# 2.net
KiCad netlist of a schematic drawn in Altium Designer
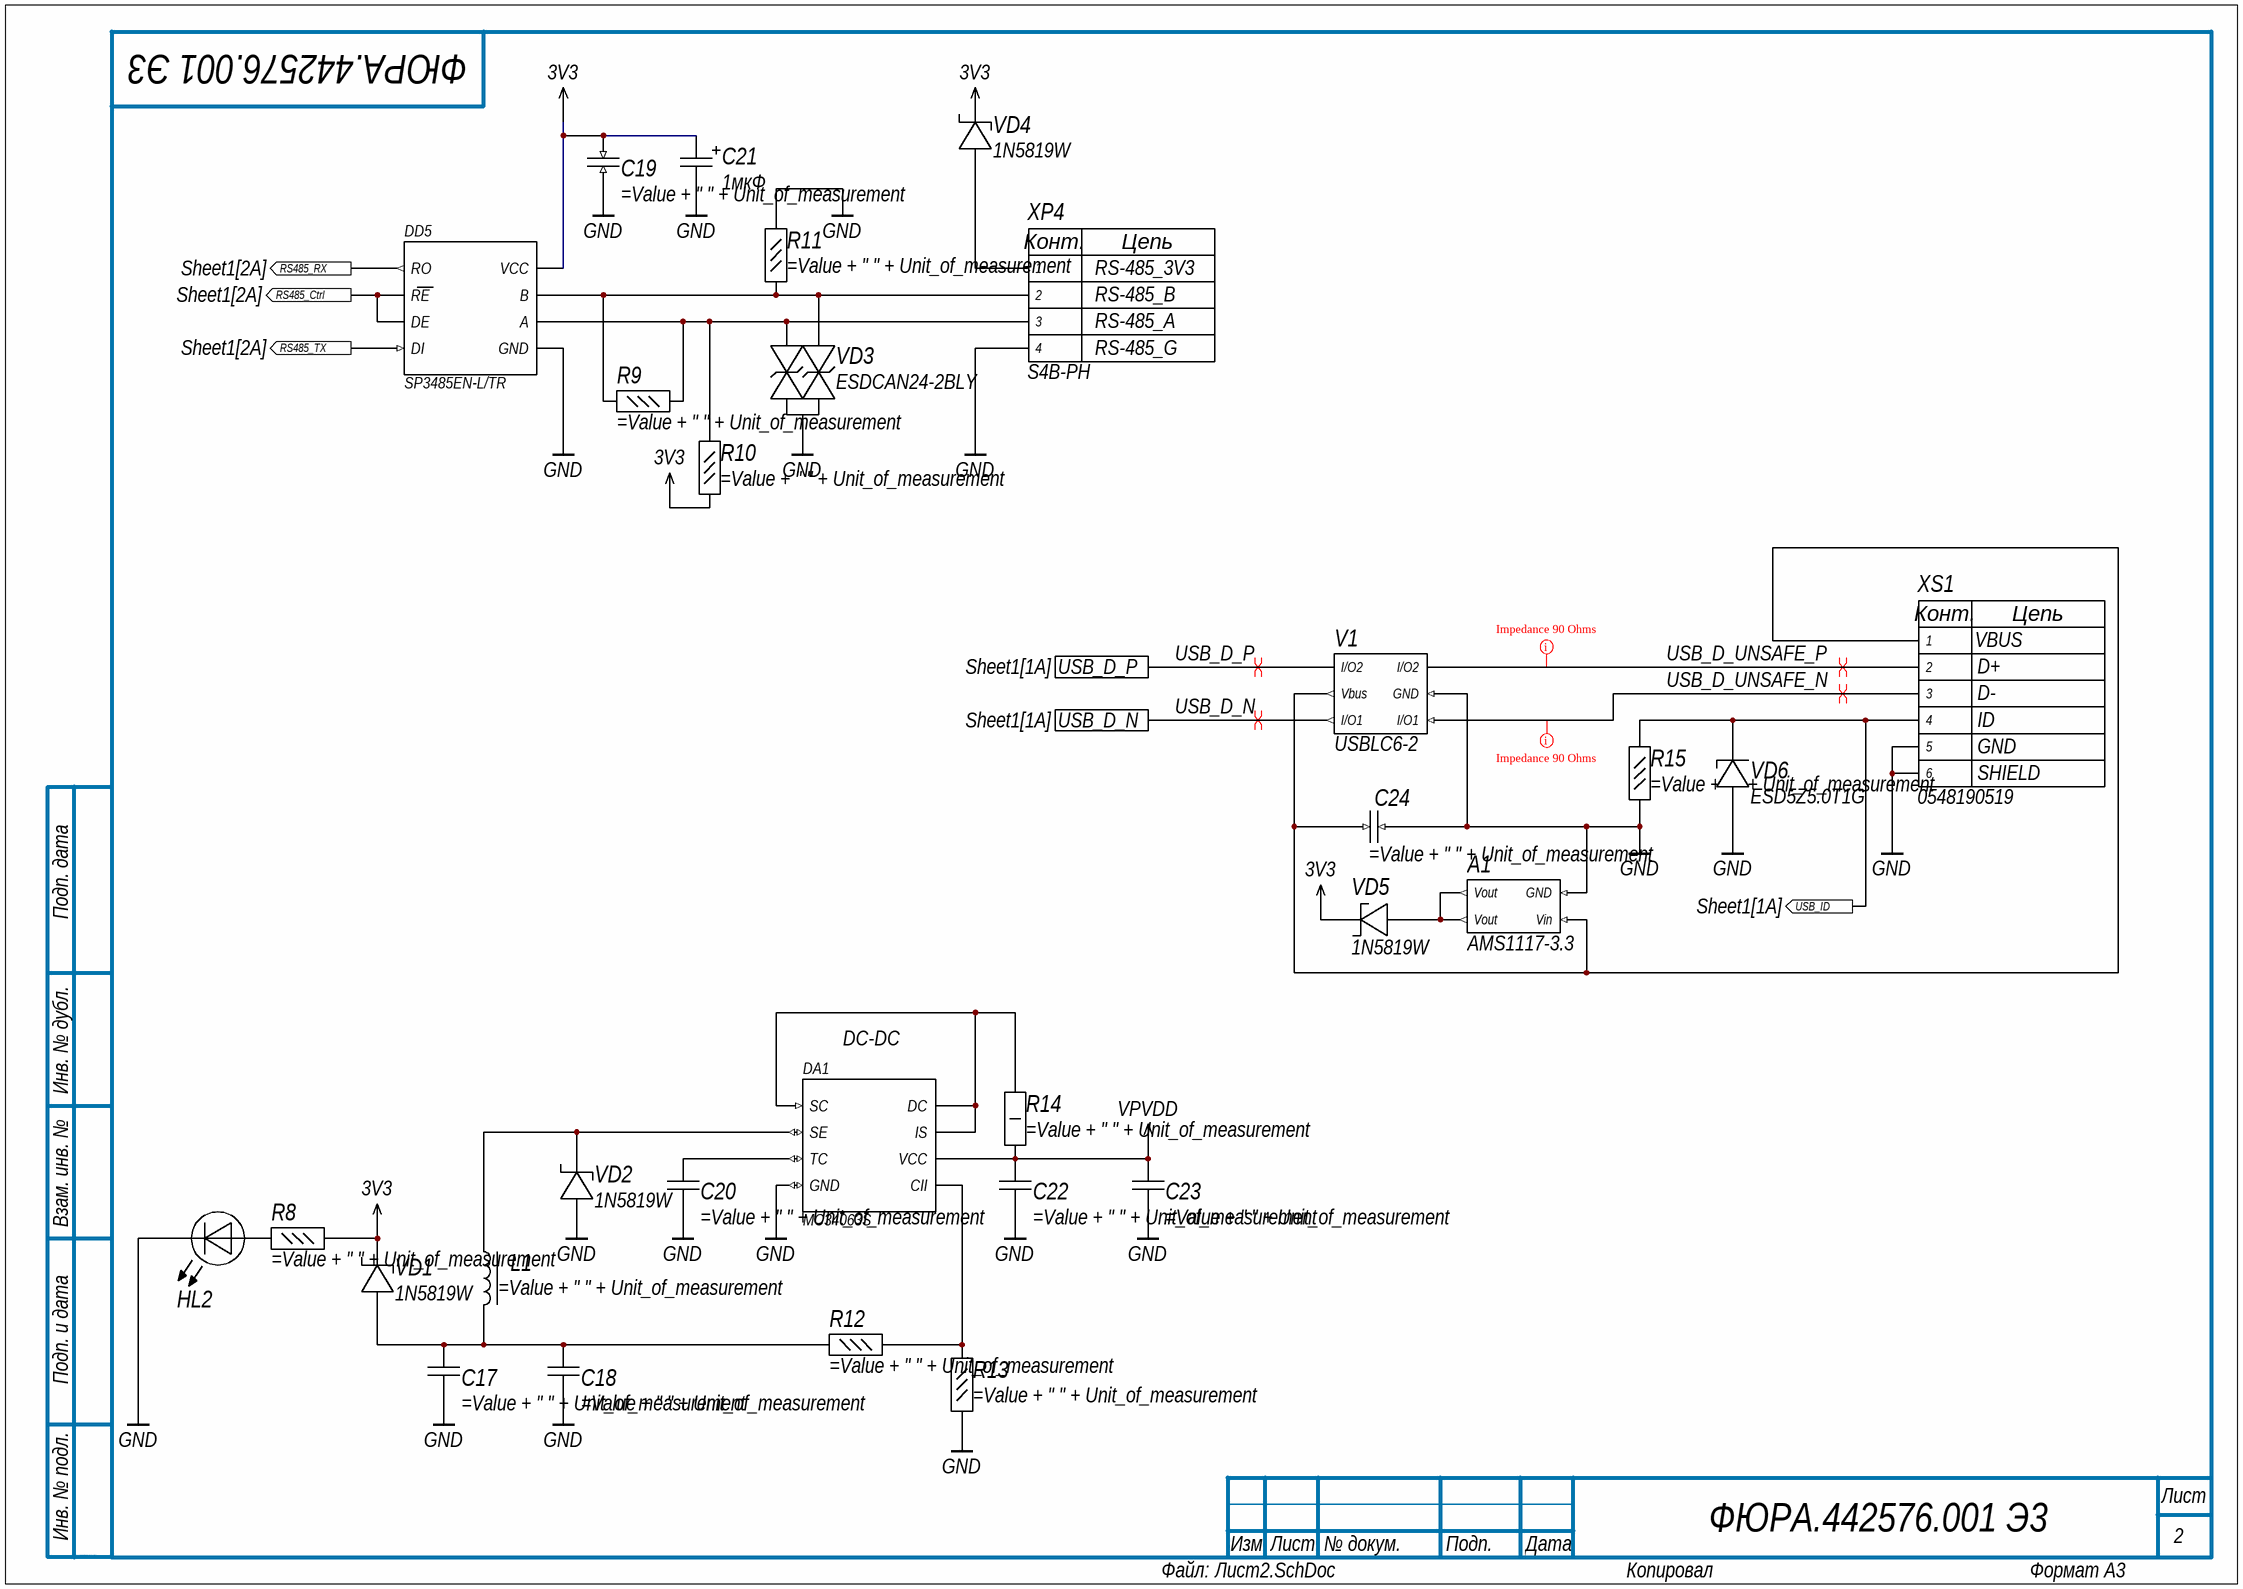
[diagram p0: Лист2.SchDoc]

(export (version "E")
  (design (tool "Eeschema 10.0.6"))
  (components
    (comp (ref "A1")
      (value "AMS1117-3.3")
      (footprint "SOT-223")
      (description "Линейный регулятор с малым падением напряжения, 1А, 3.3В [SOT-223]")
      (libsource (lib "ICs") (part "AMS1117-3.3"))
    )
    (comp (ref "C17")
      (value "10мкФ 50В")
      (footprint "CAP_1206")
      (description "Конденсатор керамический, типоразмера 1206")
      (libsource (lib "SimpleComponents") (part "CAP_1206"))
    )
    (comp (ref "C18")
      (value "10мкФ 50В")
      (footprint "CAP_1206")
      (description "Конденсатор керамический, типоразмера 1206")
      (libsource (lib "SimpleComponents") (part "CAP_1206"))
    )
    (comp (ref "C19")
      (value "100нФ")
      (footprint "CAP_0603")
      (description "Конденсатор керамический, типоразмера 0603")
      (libsource (lib "PassiveComponents") (part "CAP_0603"))
    )
    (comp (ref "C20")
      (value "3.9нФ")
      (footprint "CAP_0603")
      (description "Конденсатор керамический, типоразмера 0603")
      (libsource (lib "SimpleComponents") (part "CAP_0603"))
    )
    (comp (ref "C21")
      (value "1мкФ")
      (footprint "TECAP_A")
      (description "Описание свойств компонента")
      (libsource (lib "PassiveComponents") (part "TECAP_A"))
    )
    (comp (ref "C22")
      (value "10мкФ 50В")
      (footprint "CAP_1206")
      (description "Конденсатор керамический, типоразмера 1206")
      (libsource (lib "SimpleComponents") (part "CAP_1206"))
    )
    (comp (ref "C23")
      (value "10мкФ 50В")
      (footprint "CAP_1206")
      (description "Конденсатор керамический, типоразмера 1206")
      (libsource (lib "SimpleComponents") (part "CAP_1206"))
    )
    (comp (ref "C24")
      (value "100нФ")
      (footprint "CAP_0603")
      (description "Конденсатор керамический, типоразмера 0603")
      (libsource (lib "PassiveComponents") (part "CAP_0603"))
    )
    (comp (ref "DA1")
      (value "MC34063S")
      (footprint "SOP-8 WithoutTP")
      (libsource (lib "ICs") (part "MC34063S"))
    )
    (comp (ref "DD5")
      (value "SP3485EN-L/TR")
      (footprint "SOIC-8 WIthoutTP")
      (description "Трансивер RS485 Half-Duplex 1/1")
      (libsource (lib "ICs") (part "SP3485EN"))
    )
    (comp (ref "HL2") (value "3") (footprint "LED_0805") (libsource (lib "Complicated") (part "LED_0805_R")))
    (comp (ref "L1")
      (value "47мкГн")
      (footprint "CD54")
      (description "Резистор, типоразмера 2010")
      (libsource (lib "SimpleComponents") (part "IND_CD54"))
    )
    (comp (ref "R8")
      (value "330Ом")
      (footprint "RES_0603")
      (description "Резистор, типоразмера 0603")
      (libsource (lib "") (part "RES_0603_3"))
    )
    (comp (ref "R9")
      (value "120Ом")
      (footprint "RES_0603")
      (description "Резистор, типоразмера 0603")
      (libsource (lib "SimpleComponents") (part "RES_0603"))
    )
    (comp (ref "R10")
      (value "4.7кОм")
      (footprint "RES_0603")
      (description "Резистор, типоразмера 0603")
      (libsource (lib "") (part "RES_0603_2"))
    )
    (comp (ref "R11")
      (value "4.7кОм")
      (footprint "RES_0603")
      (description "Резистор, типоразмера 0603")
      (libsource (lib "") (part "RES_0603_1"))
    )
    (comp (ref "R12")
      (value "8.2кОм 1%")
      (footprint "RES_0603")
      (description "Резистор, типоразмера 0603")
      (libsource (lib "SimpleComponents") (part "RES_0603"))
    )
    (comp (ref "R13")
      (value "5кОм 1%")
      (footprint "RES_0603")
      (description "Резистор, типоразмера 0603")
      (libsource (lib "") (part "RES_0603_1"))
    )
    (comp (ref "R14")
      (value "0.2Ом 1%")
      (footprint "RES_2512")
      (description "Резистор, типоразмера 2512")
      (libsource (lib "SimpleComponents") (part "RES_2512"))
    )
    (comp (ref "R15")
      (value "100кОм")
      (footprint "RES_0603")
      (description "Резистор, типоразмера 0603")
      (libsource (lib "") (part "RES_0603_1"))
    )
    (comp (ref "V1")
      (value "USBLC6-2")
      (footprint "SOT23-6")
      (description "Защита интерфейса USB от электростатических разрядов [SOT-23-6]")
      (libsource (lib "ICs") (part "USBLC6-2"))
    )
    (comp (ref "VD1")
      (value "1N5819W")
      (footprint "SOD-123")
      (description "Диод Шоттки, 40 В, 0.35 А, SOD-123")
      (libsource (lib "SimpleComponents") (part "1N5819W"))
    )
    (comp (ref "VD2")
      (value "1N5819W")
      (footprint "SOD-123")
      (description "Диод Шоттки, 40 В, 0.35 А, SOD-123")
      (libsource (lib "SimpleComponents") (part "1N5819W"))
    )
    (comp (ref "VD3")
      (value "ESDCAN24-2BLY")
      (footprint "SOT23")
      (description "Устройство защиты CAN шины от ESD, 2 защитных диода [SOT-23-3]")
      (libsource (lib "Complicated") (part "ESDCAN24-2BLY"))
    )
    (comp (ref "VD4")
      (value "1N5819W")
      (footprint "SOD-123")
      (description "Диод Шоттки, 40 В, 0.35 А, SOD-123")
      (libsource (lib "SimpleComponents") (part "1N5819W"))
    )
    (comp (ref "VD5")
      (value "1N5819W")
      (footprint "SOD-123")
      (description "Диод Шоттки, 40 В, 0.35 А, SOD-123")
      (libsource (lib "Complicated") (part "1N5819W"))
    )
    (comp (ref "VD6")
      (value "ESD5Z5.0T1G")
      (footprint "SOD-523")
      (description "Устройство защиты от ESD, защитный диод, 5В [SOD-523]")
      (libsource (lib "Complicated") (part "ESD5Z5.0T1G"))
    )
    (comp (ref "XP4")
      (value "S4B-PH")
      (footprint "S4B-PH")
      (description "JST PH 4pin 2 mm pitch; horizontal; through hole OR full smd; S4B-PH-SM4-TB")
      (libsource (lib "SimpleComponents") (part "S4B-PH"))
    )
    (comp (ref "XS1")
      (value "0548190519")
      (footprint "USB_Mini_B_TH")
      (description "USB - mini B USB 2.0 OTG Receptacle Connector 5 Position Through Hole, Right Angle")
      (libsource (lib "SimpleComponents") (part "0548190519"))
    )
  )
  (nets
    (net (code "1") (name "/RS485_Ctrl") (class "Default")
      (node (ref "DD5") (pin "2") (pinfunction "RE_2") (pintype "passive"))
      (node (ref "DD5") (pin "3") (pinfunction "DE_3") (pintype "passive"))
    )
    (net (code "2") (name "/RS485_RX") (class "Default")
      (node (ref "DD5") (pin "1") (pinfunction "RO_1") (pintype "output"))
    )
    (net (code "3") (name "/RS485_TX") (class "Default")
      (node (ref "DD5") (pin "4") (pinfunction "DI_4") (pintype "input"))
    )
    (net (code "4") (name "/USB_D_N") (class "Default")
      (node (ref "V1") (pin "6") (pinfunction "I/O1_6") (pintype "output"))
    )
    (net (code "5") (name "/USB_D_P") (class "Default")
      (node (ref "V1") (pin "4") (pinfunction "I/O2_4") (pintype "power_in"))
    )
    (net (code "6") (name "/USB_D_UNSAFE_N") (class "Default")
      (node (ref "V1") (pin "1") (pinfunction "I/O1_1") (pintype "input"))
      (node (ref "XS1") (pin "4") (pinfunction "3_4") (pintype "passive"))
    )
    (net (code "7") (name "/USB_D_UNSAFE_P") (class "Default")
      (node (ref "V1") (pin "3") (pinfunction "I/O2_3") (pintype "power_in"))
      (node (ref "XS1") (pin "3") (pinfunction "2_3") (pintype "passive"))
    )
    (net (code "8") (name "/USB_ID") (class "Default")
      (node (ref "R15") (pin "2") (pinfunction "2_2") (pintype "passive"))
      (node (ref "VD6") (pin "1") (pinfunction "1_1") (pintype "passive"))
      (node (ref "XS1") (pin "2") (pinfunction "4_2") (pintype "passive"))
    )
    (net (code "9") (name "3V3") (class "Default")
      (node (ref "C19") (pin "2") (pintype "input"))
      (node (ref "C21") (pin "1") (pintype "passive"))
      (node (ref "DD5") (pin "8") (pinfunction "VCC_8") (pintype "power_in"))
      (node (ref "R10") (pin "2") (pinfunction "2_2") (pintype "passive"))
      (node (ref "R8") (pin "1") (pinfunction "1_1") (pintype "passive"))
      (node (ref "VD1") (pin "1") (pinfunction "1_1") (pintype "passive"))
      (node (ref "VD4") (pin "1") (pinfunction "1_1") (pintype "passive"))
      (node (ref "VD5") (pin "1") (pinfunction "1_1") (pintype "passive"))
    )
    (net (code "10") (name "GND") (class "Default")
      (node (ref "A1") (pin "1") (pinfunction "GND_1") (pintype "input"))
      (node (ref "C17") (pin "1") (pintype "passive"))
      (node (ref "C18") (pin "1") (pintype "passive"))
      (node (ref "C19") (pin "1") (pintype "input"))
      (node (ref "C20") (pin "1") (pintype "passive"))
      (node (ref "C21") (pin "2") (pintype "passive"))
      (node (ref "C22") (pin "1") (pintype "passive"))
      (node (ref "C23") (pin "1") (pintype "passive"))
      (node (ref "C24") (pin "1") (pintype "input"))
      (node (ref "DA1") (pin "4") (pinfunction "GND_4") (pintype "bidirectional"))
      (node (ref "DD5") (pin "5") (pinfunction "GND_5") (pintype "power_in"))
      (node (ref "HL2") (pin "C") (pinfunction "1_C") (pintype "passive"))
      (node (ref "R11") (pin "2") (pinfunction "2_2") (pintype "passive"))
      (node (ref "R13") (pin "1") (pinfunction "1_1") (pintype "passive"))
      (node (ref "R15") (pin "1") (pinfunction "1_1") (pintype "passive"))
      (node (ref "V1") (pin "2") (pinfunction "GND_2") (pintype "input"))
      (node (ref "VD2") (pin "2") (pinfunction "2_2") (pintype "passive"))
      (node (ref "VD3") (pin "3") (pinfunction "3_3") (pintype "passive"))
      (node (ref "VD6") (pin "2") (pinfunction "2_2") (pintype "passive"))
      (node (ref "XP4") (pin "4") (pinfunction "4_4") (pintype "passive"))
      (node (ref "XS1") (pin "1") (pinfunction "5_1") (pintype "passive"))
      (node (ref "XS1") (pin "6") (pinfunction "6_6") (pintype "passive"))
    )
    (net (code "11") (name "Net-(A1-Vin)") (class "Default")
      (node (ref "A1") (pin "3") (pinfunction "Vin_3") (pintype "input"))
      (node (ref "C24") (pin "2") (pintype "input"))
      (node (ref "V1") (pin "5") (pinfunction "Vbus_5") (pintype "output"))
      (node (ref "XS1") (pin "5") (pinfunction "1_5") (pintype "passive"))
    )
    (net (code "12") (name "Net-(A1-Vout-Pad2)") (class "Default")
      (node (ref "A1") (pin "2") (pinfunction "Vout_2") (pintype "output"))
      (node (ref "A1") (pin "4") (pinfunction "Vout_4") (pintype "output"))
      (node (ref "VD5") (pin "2") (pinfunction "2_2") (pintype "passive"))
    )
    (net (code "13") (name "Net-(C17-Pad2)") (class "Default")
      (node (ref "C17") (pin "2") (pintype "passive"))
      (node (ref "C18") (pin "2") (pintype "passive"))
      (node (ref "L1") (pin "2") (pinfunction "2_2") (pintype "passive"))
      (node (ref "R12") (pin "1") (pinfunction "1_1") (pintype "passive"))
      (node (ref "VD1") (pin "2") (pinfunction "2_2") (pintype "passive"))
    )
    (net (code "14") (name "Net-(DA1-CII)") (class "Default")
      (node (ref "DA1") (pin "5") (pinfunction "CII_5") (pintype "power_in"))
      (node (ref "R12") (pin "2") (pinfunction "2_2") (pintype "passive"))
      (node (ref "R13") (pin "2") (pinfunction "2_2") (pintype "passive"))
    )
    (net (code "15") (name "Net-(DA1-DC)") (class "Default")
      (node (ref "DA1") (pin "1") (pinfunction "SC_1") (pintype "input"))
      (node (ref "DA1") (pin "7") (pinfunction "IS_7") (pintype "power_in"))
      (node (ref "DA1") (pin "8") (pinfunction "DC_8") (pintype "power_in"))
      (node (ref "R14") (pin "2") (pinfunction "2_2") (pintype "passive"))
    )
    (net (code "16") (name "Net-(DA1-SE)") (class "Default")
      (node (ref "DA1") (pin "2") (pinfunction "SE_2") (pintype "bidirectional"))
      (node (ref "L1") (pin "1") (pinfunction "1_1") (pintype "passive"))
      (node (ref "VD2") (pin "1") (pinfunction "1_1") (pintype "passive"))
    )
    (net (code "17") (name "Net-(DA1-TC)") (class "Default")
      (node (ref "C20") (pin "2") (pintype "passive"))
      (node (ref "DA1") (pin "3") (pinfunction "TC_3") (pintype "bidirectional"))
    )
    (net (code "18") (name "Net-(DD5-A)") (class "Default")
      (node (ref "DD5") (pin "6") (pinfunction "A_6") (pintype "power_in"))
      (node (ref "R10") (pin "1") (pinfunction "1_1") (pintype "passive"))
      (node (ref "R9") (pin "2") (pinfunction "2_2") (pintype "passive"))
      (node (ref "VD3") (pin "2") (pinfunction "2_2") (pintype "passive"))
      (node (ref "XP4") (pin "3") (pinfunction "3_3") (pintype "passive"))
    )
    (net (code "19") (name "Net-(DD5-B)") (class "Default")
      (node (ref "DD5") (pin "7") (pinfunction "B_7") (pintype "power_in"))
      (node (ref "R11") (pin "1") (pinfunction "1_1") (pintype "passive"))
      (node (ref "R9") (pin "1") (pinfunction "1_1") (pintype "passive"))
      (node (ref "VD3") (pin "1") (pinfunction "1_1") (pintype "passive"))
      (node (ref "XP4") (pin "2") (pinfunction "2_2") (pintype "passive"))
    )
    (net (code "20") (name "Net-(HL2-2)") (class "Default")
      (node (ref "HL2") (pin "A") (pinfunction "2_A") (pintype "passive"))
      (node (ref "R8") (pin "2") (pinfunction "2_2") (pintype "passive"))
    )
    (net (code "21") (name "Net-(VD4-Pad2)") (class "Default")
      (node (ref "VD4") (pin "2") (pinfunction "2_2") (pintype "passive"))
      (node (ref "XP4") (pin "1") (pinfunction "1_1") (pintype "passive"))
    )
    (net (code "22") (name "VPVDD") (class "Default")
      (node (ref "C22") (pin "2") (pintype "passive"))
      (node (ref "C23") (pin "2") (pintype "passive"))
      (node (ref "DA1") (pin "6") (pinfunction "VCC_6") (pintype "power_in"))
      (node (ref "R14") (pin "1") (pinfunction "1_1") (pintype "passive"))
    )
  )
)
